# Sheet1.net
KiCad netlist of a schematic drawn in Altium Designer
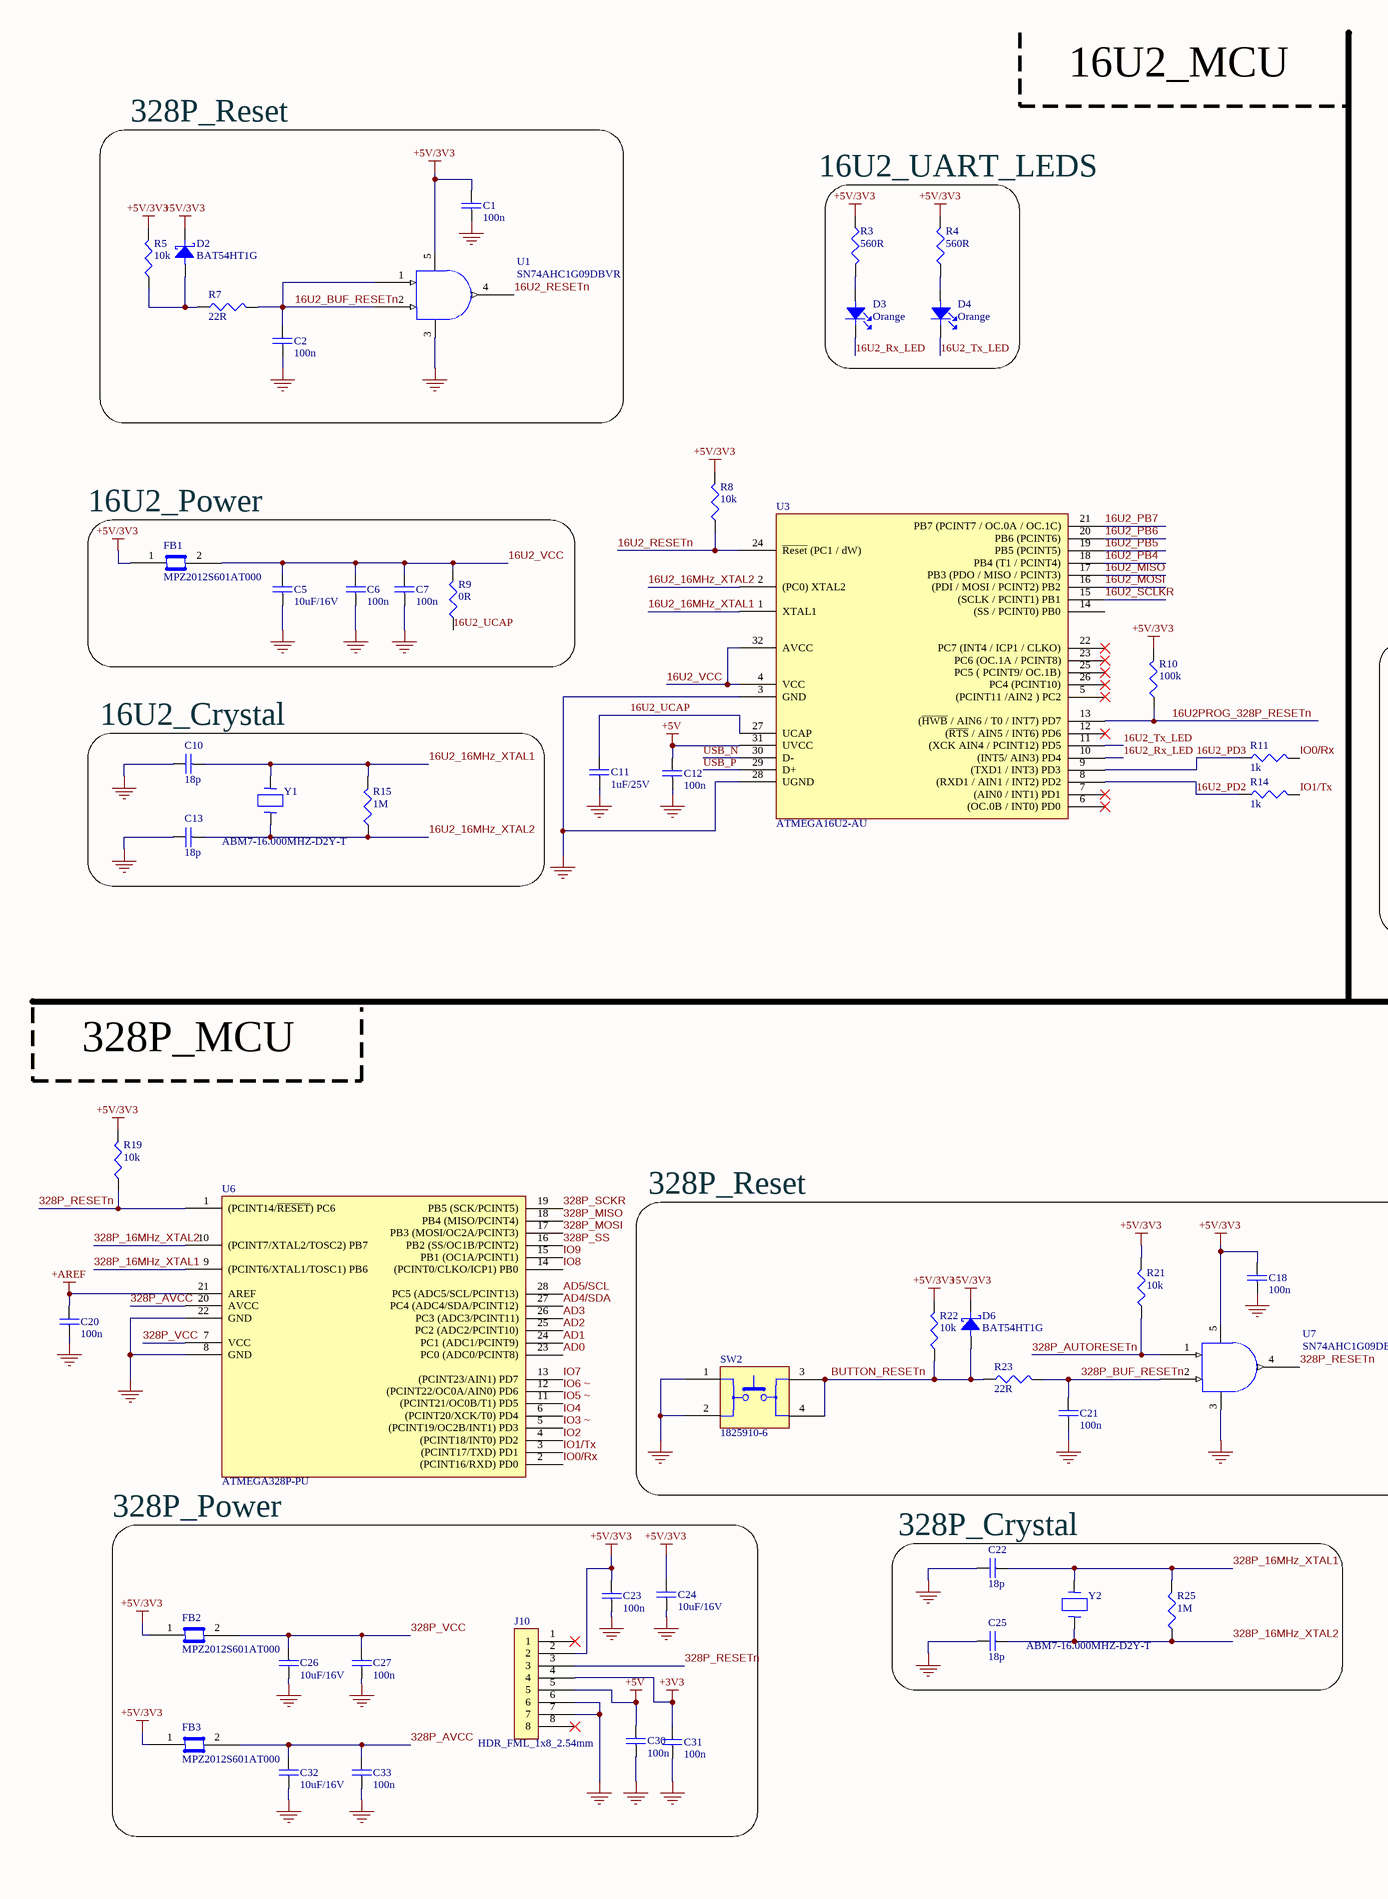
[diagram p0: Sheet1.SchDoc, left]
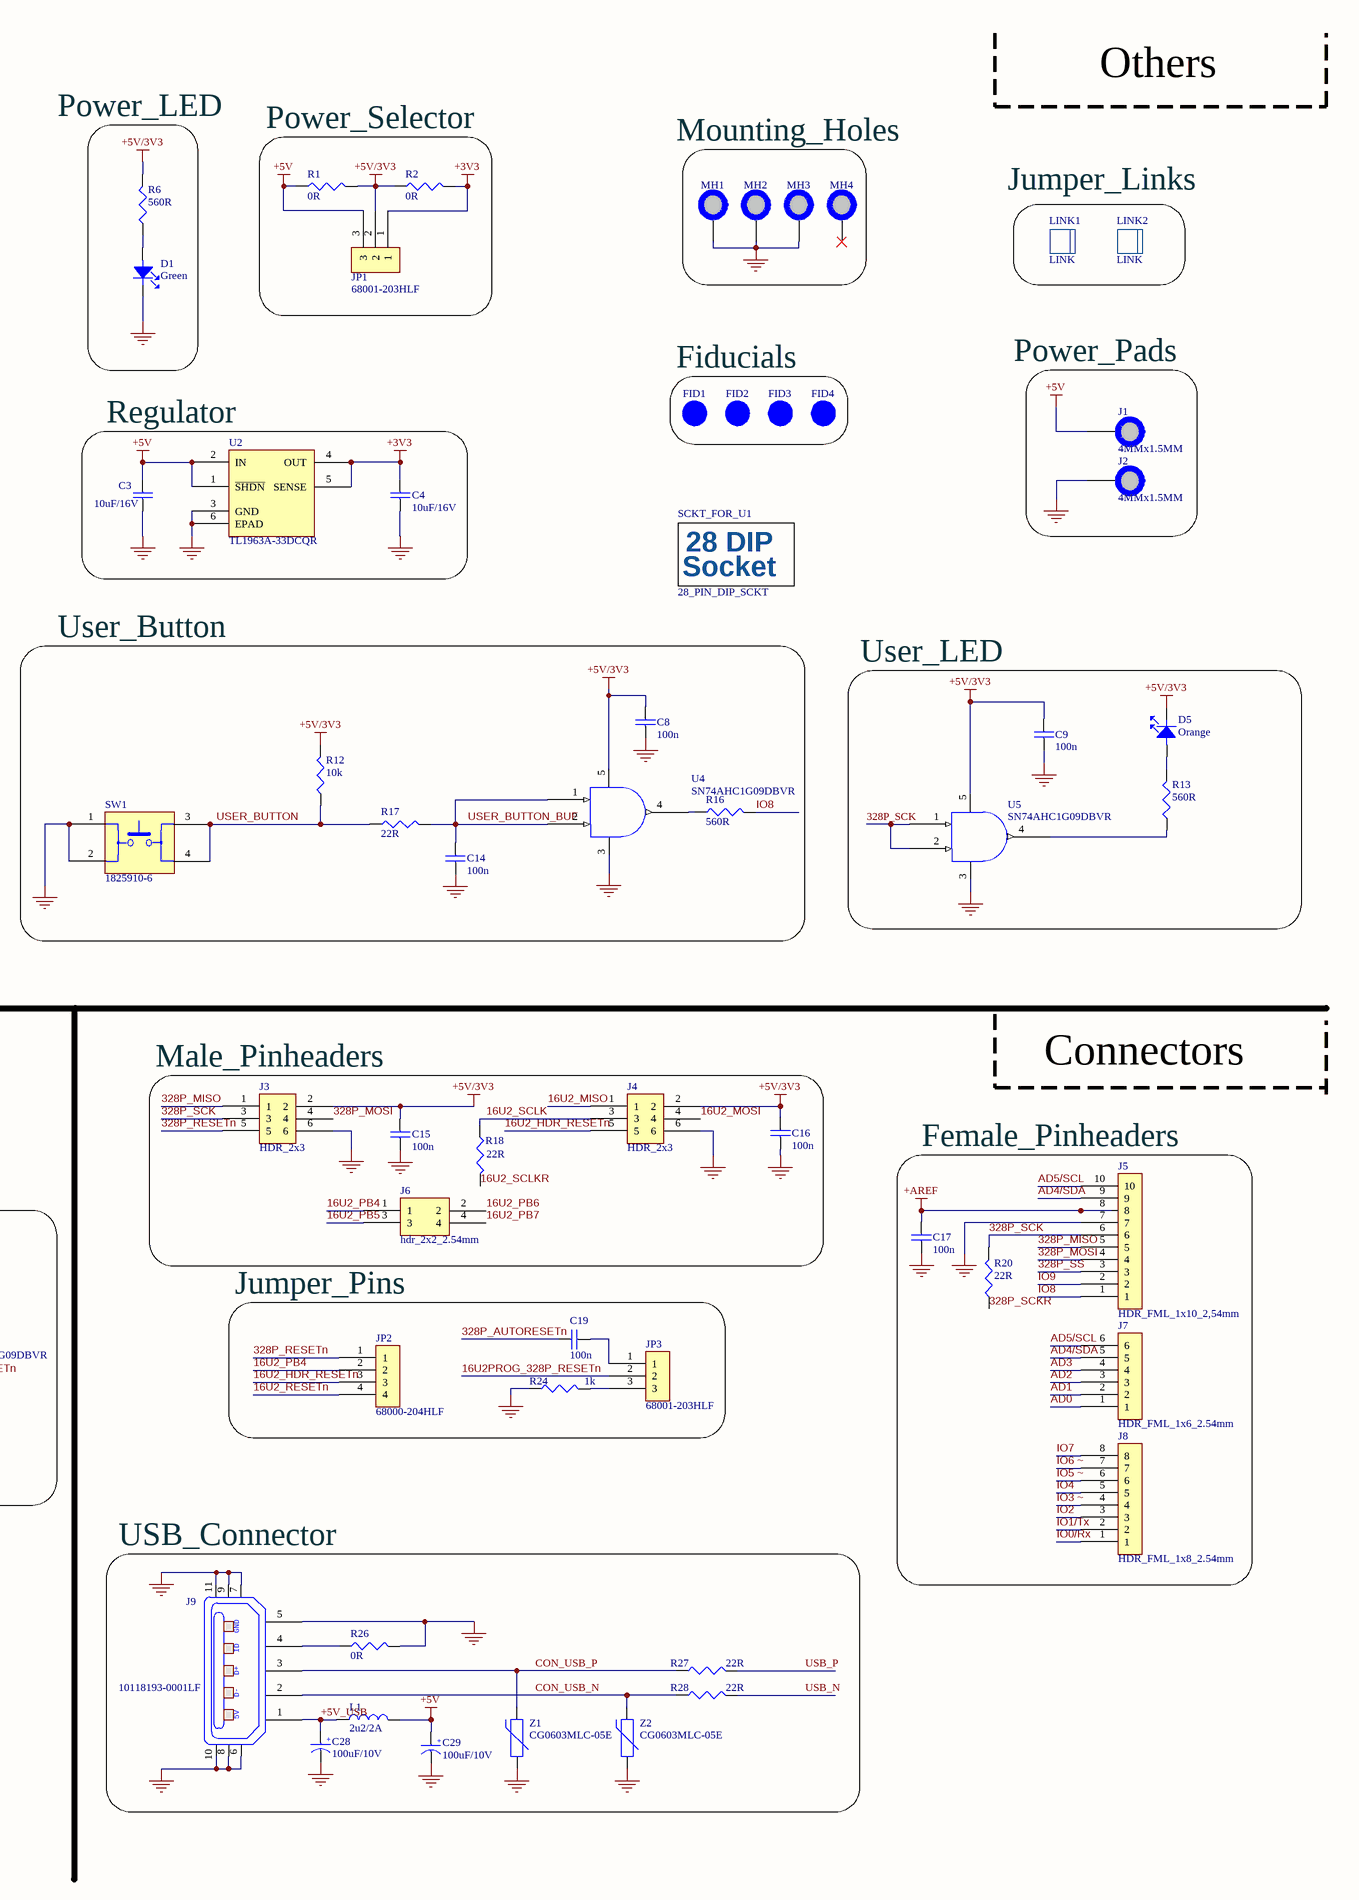
[diagram p1: Sheet1.SchDoc, right]

(export (version "E")
  (design (tool "Eeschema 10.0.6"))
  (components
    (comp (ref "C1")
      (value "100n")
      (footprint "C0805_100n")
      (description "Multilayer Ceramic Capacitor, 0.1 uF, 50 V, ± 10%, X7R, 0805 [2012 Metric]")
      (fields
        (field (name "MANUFACTURER") "TDK")
        (field (name "MANUFACTURER PART NUMBER") "C2012X7R1H104K085AA")
      )
      (libsource (lib "Schlib1") (part "capacitor_100n"))
    )
    (comp (ref "C2")
      (value "100n")
      (footprint "C0805_100n")
      (description "Multilayer Ceramic Capacitor, 0.1 uF, 50 V, ± 10%, X7R, 0805 [2012 Metric]")
      (fields
        (field (name "MANUFACTURER") "TDK")
        (field (name "MANUFACTURER PART NUMBER") "C2012X7R1H104K085AA")
      )
      (libsource (lib "Schlib1") (part "C2012X7R1H104K085AA"))
    )
    (comp (ref "C3")
      (value "10uF/16V")
      (footprint "C0805_10u")
      (description "C Series 0805 10 uF 16 V ±10 % Tolerance X5R SMT Multilayer Ceramic Capacitor")
      (fields
        (field (name "MANUFACTURER") "TDK")
        (field (name "MANUFACTURER PART NUMBER") "C2012X5R1C106K085AC")
      )
      (libsource (lib "Schlib1") (part "capacitor_10uF_16V"))
    )
    (comp (ref "C4")
      (value "10uF/16V")
      (footprint "C0805_10u")
      (description "C Series 0805 10 uF 16 V ±10 % Tolerance X5R SMT Multilayer Ceramic Capacitor")
      (fields
        (field (name "MANUFACTURER") "TDK")
        (field (name "MANUFACTURER PART NUMBER") "C2012X5R1C106K085AC")
      )
      (libsource (lib "Schlib1") (part "capacitor_10uF_16V"))
    )
    (comp (ref "C5")
      (value "10uF/16V")
      (footprint "C0805_10u")
      (description "C Series 0805 10 uF 16 V ±10 % Tolerance X5R SMT Multilayer Ceramic Capacitor")
      (fields
        (field (name "MANUFACTURER") "TDK")
        (field (name "MANUFACTURER PART NUMBER") "C2012X5R1C106K085AC")
      )
      (libsource (lib "Schlib1") (part "C2012X5R1C106K085AC"))
    )
    (comp (ref "C6")
      (value "100n")
      (footprint "C0805_100n")
      (description "Multilayer Ceramic Capacitor, 0.1 uF, 50 V, ± 10%, X7R, 0805 [2012 Metric]")
      (fields
        (field (name "MANUFACTURER") "TDK")
        (field (name "MANUFACTURER PART NUMBER") "C2012X7R1H104K085AA")
      )
      (libsource (lib "Schlib1") (part "C2012X7R1H104K085AA"))
    )
    (comp (ref "C7")
      (value "100n")
      (footprint "C0805_100n")
      (description "Multilayer Ceramic Capacitor, 0.1 uF, 50 V, ± 10%, X7R, 0805 [2012 Metric]")
      (fields
        (field (name "MANUFACTURER") "TDK")
        (field (name "MANUFACTURER PART NUMBER") "C2012X7R1H104K085AA")
      )
      (libsource (lib "Schlib1") (part "C2012X7R1H104K085AA"))
    )
    (comp (ref "C8")
      (value "100n")
      (footprint "C0805_100n")
      (description "Multilayer Ceramic Capacitor, 0.1 uF, 50 V, ± 10%, X7R, 0805 [2012 Metric]")
      (fields
        (field (name "MANUFACTURER") "TDK")
        (field (name "MANUFACTURER PART NUMBER") "C2012X7R1H104K085AA")
      )
      (libsource (lib "Schlib1") (part "capacitor_100n"))
    )
    (comp (ref "C9")
      (value "100n")
      (footprint "C0805_100n")
      (description "Multilayer Ceramic Capacitor, 0.1 uF, 50 V, ± 10%, X7R, 0805 [2012 Metric]")
      (fields
        (field (name "MANUFACTURER") "TDK")
        (field (name "MANUFACTURER PART NUMBER") "C2012X7R1H104K085AA")
      )
      (libsource (lib "Schlib1") (part "capacitor_100n"))
    )
    (comp (ref "C10")
      (value "18p")
      (footprint "C0805_100n")
      (description "Multilayer Ceramic Capacitor, 18 pF, 50 V, ± 10%, C0G (NP0), 0805 [2012 Metric]")
      (fields
        (field (name "MANUFACTURER") "KEMET")
        (field (name "MANUFACTURER PART NUMBER") "C0805C180K5GACTU")
      )
      (libsource (lib "Schlib1") (part "C0805C180K5GACTU"))
    )
    (comp (ref "C11")
      (value "1uF/25V")
      (footprint "C0805_10u")
      (description "Multilayer Ceramic Capacitor, 1 uF, 25 V, ± 10%, X7R, 0805 [2012 Metric]")
      (fields
        (field (name "MANUFACTURER") "TDK")
        (field (name "MANUFACTURER PART NUMBER") "CGA4J3X7R1E105K125AB")
      )
      (libsource (lib "Schlib1") (part "capacitor_1uF"))
    )
    (comp (ref "C12")
      (value "100n")
      (footprint "C0805_100n")
      (description "Multilayer Ceramic Capacitor, 0.1 uF, 50 V, ± 10%, X7R, 0805 [2012 Metric]")
      (fields
        (field (name "MANUFACTURER") "TDK")
        (field (name "MANUFACTURER PART NUMBER") "C2012X7R1H104K085AA")
      )
      (libsource (lib "Schlib1") (part "C2012X7R1H104K085AA"))
    )
    (comp (ref "C13")
      (value "18p")
      (footprint "C0805_100n")
      (description "Multilayer Ceramic Capacitor, 18 pF, 50 V, ± 10%, C0G (NP0), 0805 [2012 Metric]")
      (fields
        (field (name "MANUFACTURER") "KEMET")
        (field (name "MANUFACTURER PART NUMBER") "C0805C180K5GACTU")
      )
      (libsource (lib "Schlib1") (part "C0805C180K5GACTU"))
    )
    (comp (ref "C14")
      (value "100n")
      (footprint "C0805_100n")
      (description "Multilayer Ceramic Capacitor, 0.1 uF, 50 V, ± 10%, X7R, 0805 [2012 Metric]")
      (fields
        (field (name "MANUFACTURER") "TDK")
        (field (name "MANUFACTURER PART NUMBER") "C2012X7R1H104K085AA")
      )
      (libsource (lib "Schlib1") (part "C2012X7R1H104K085AA"))
    )
    (comp (ref "C15")
      (value "100n")
      (footprint "C0805_100n")
      (description "Multilayer Ceramic Capacitor, 0.1 uF, 50 V, ± 10%, X7R, 0805 [2012 Metric]")
      (fields
        (field (name "MANUFACTURER") "TDK")
        (field (name "MANUFACTURER PART NUMBER") "C2012X7R1H104K085AA")
      )
      (libsource (lib "Schlib1") (part "C2012X7R1H104K085AA"))
    )
    (comp (ref "C16")
      (value "100n")
      (footprint "C0805_100n")
      (description "Multilayer Ceramic Capacitor, 0.1 uF, 50 V, ± 10%, X7R, 0805 [2012 Metric]")
      (fields
        (field (name "MANUFACTURER") "TDK")
        (field (name "MANUFACTURER PART NUMBER") "C2012X7R1H104K085AA")
      )
      (libsource (lib "Schlib1") (part "C2012X7R1H104K085AA"))
    )
    (comp (ref "C17")
      (value "100n")
      (footprint "C0805_100n")
      (description "Multilayer Ceramic Capacitor, 0.1 uF, 50 V, ± 10%, X7R, 0805 [2012 Metric]")
      (fields
        (field (name "MANUFACTURER") "TDK")
        (field (name "MANUFACTURER PART NUMBER") "C2012X7R1H104K085AA")
      )
      (libsource (lib "Schlib1") (part "C2012X7R1H104K085AA"))
    )
    (comp (ref "C18")
      (value "100n")
      (footprint "C0805_100n")
      (description "Multilayer Ceramic Capacitor, 0.1 uF, 50 V, ± 10%, X7R, 0805 [2012 Metric]")
      (fields
        (field (name "MANUFACTURER") "TDK")
        (field (name "MANUFACTURER PART NUMBER") "C2012X7R1H104K085AA")
      )
      (libsource (lib "Schlib1") (part "capacitor_100n"))
    )
    (comp (ref "C19")
      (value "100n")
      (footprint "C0805_100n")
      (description "Multilayer Ceramic Capacitor, 0.1 uF, 50 V, ± 10%, X7R, 0805 [2012 Metric]")
      (fields
        (field (name "MANUFACTURER") "TDK")
        (field (name "MANUFACTURER PART NUMBER") "C2012X7R1H104K085AA")
      )
      (libsource (lib "Schlib1") (part "capacitor_100n"))
    )
    (comp (ref "C20")
      (value "100n")
      (footprint "C0805_100n")
      (description "Multilayer Ceramic Capacitor, 0.1 uF, 50 V, ± 10%, X7R, 0805 [2012 Metric]")
      (fields
        (field (name "MANUFACTURER") "TDK")
        (field (name "MANUFACTURER PART NUMBER") "C2012X7R1H104K085AA")
      )
      (libsource (lib "Schlib1") (part "C2012X7R1H104K085AA"))
    )
    (comp (ref "C21")
      (value "100n")
      (footprint "C0805_100n")
      (description "Multilayer Ceramic Capacitor, 0.1 uF, 50 V, ± 10%, X7R, 0805 [2012 Metric]")
      (fields
        (field (name "MANUFACTURER") "TDK")
        (field (name "MANUFACTURER PART NUMBER") "C2012X7R1H104K085AA")
      )
      (libsource (lib "Schlib1") (part "C2012X7R1H104K085AA"))
    )
    (comp (ref "C22")
      (value "18p")
      (footprint "C0805_100n")
      (description "Multilayer Ceramic Capacitor, 18 pF, 50 V, ± 10%, C0G (NP0), 0805 [2012 Metric]")
      (fields
        (field (name "MANUFACTURER") "KEMET")
        (field (name "MANUFACTURER PART NUMBER") "C0805C180K5GACTU")
      )
      (libsource (lib "Schlib1") (part "C0805C180K5GACTU"))
    )
    (comp (ref "C23")
      (value "100n")
      (footprint "C0805_100n")
      (description "Multilayer Ceramic Capacitor, 0.1 uF, 50 V, ± 10%, X7R, 0805 [2012 Metric]")
      (fields
        (field (name "MANUFACTURER") "TDK")
        (field (name "MANUFACTURER PART NUMBER") "C2012X7R1H104K085AA")
      )
      (libsource (lib "Schlib1") (part "C2012X7R1H104K085AA"))
    )
    (comp (ref "C24")
      (value "10uF/16V")
      (footprint "C0805_10u")
      (description "C Series 0805 10 uF 16 V ±10 % Tolerance X5R SMT Multilayer Ceramic Capacitor")
      (fields
        (field (name "MANUFACTURER") "TDK")
        (field (name "MANUFACTURER PART NUMBER") "C2012X5R1C106K085AC")
      )
      (libsource (lib "Schlib1") (part "C2012X5R1C106K085AC"))
    )
    (comp (ref "C25")
      (value "18p")
      (footprint "C0805_100n")
      (description "Multilayer Ceramic Capacitor, 18 pF, 50 V, ± 10%, C0G (NP0), 0805 [2012 Metric]")
      (fields
        (field (name "MANUFACTURER") "KEMET")
        (field (name "MANUFACTURER PART NUMBER") "C0805C180K5GACTU")
      )
      (libsource (lib "Schlib1") (part "C0805C180K5GACTU"))
    )
    (comp (ref "C26")
      (value "10uF/16V")
      (footprint "C0805_10u")
      (description "C Series 0805 10 uF 16 V ±10 % Tolerance X5R SMT Multilayer Ceramic Capacitor")
      (fields
        (field (name "MANUFACTURER") "TDK")
        (field (name "MANUFACTURER PART NUMBER") "C2012X5R1C106K085AC")
      )
      (libsource (lib "Schlib1") (part "C2012X5R1C106K085AC"))
    )
    (comp (ref "C27")
      (value "100n")
      (footprint "C0805_100n")
      (description "Multilayer Ceramic Capacitor, 0.1 uF, 50 V, ± 10%, X7R, 0805 [2012 Metric]")
      (fields
        (field (name "MANUFACTURER") "TDK")
        (field (name "MANUFACTURER PART NUMBER") "C2012X7R1H104K085AA")
      )
      (libsource (lib "Schlib1") (part "C2012X7R1H104K085AA"))
    )
    (comp (ref "C28")
      (value "100uF/10V")
      (footprint "C_ALU_C_SIZE")
      (description "Cap Aluminum Polymer 100uF 10VDC 20% (5 X 6mm) SMD 0.035 Ohm 1800mA 2000h 105C Automotive T/R")
      (fields
        (field (name "MANUFACTURER") "Nichicon")
        (field (name "MANUFACTURER PART NUMBER") "PCG1A101MCL1GS")
      )
      (libsource (lib "Schlib1") (part "capacitor_100uF/10V"))
    )
    (comp (ref "C29")
      (value "100uF/10V")
      (footprint "C_ALU_C_SIZE")
      (description "Cap Aluminum Polymer 100uF 10VDC 20% (5 X 6mm) SMD 0.035 Ohm 1800mA 2000h 105C Automotive T/R")
      (fields
        (field (name "MANUFACTURER") "Nichicon")
        (field (name "MANUFACTURER PART NUMBER") "PCG1A101MCL1GS")
      )
      (libsource (lib "Schlib1") (part "capacitor_100uF/10V"))
    )
    (comp (ref "C30")
      (value "100n")
      (footprint "C0805_100n")
      (description "Multilayer Ceramic Capacitor, 0.1 uF, 50 V, ± 10%, X7R, 0805 [2012 Metric]")
      (fields
        (field (name "MANUFACTURER") "TDK")
        (field (name "MANUFACTURER PART NUMBER") "C2012X7R1H104K085AA")
      )
      (libsource (lib "Schlib1") (part "C2012X7R1H104K085AA"))
    )
    (comp (ref "C31")
      (value "100n")
      (footprint "C0805_100n")
      (description "Multilayer Ceramic Capacitor, 0.1 uF, 50 V, ± 10%, X7R, 0805 [2012 Metric]")
      (fields
        (field (name "MANUFACTURER") "TDK")
        (field (name "MANUFACTURER PART NUMBER") "C2012X7R1H104K085AA")
      )
      (libsource (lib "Schlib1") (part "C2012X7R1H104K085AA"))
    )
    (comp (ref "C32")
      (value "10uF/16V")
      (footprint "C0805_10u")
      (description "C Series 0805 10 uF 16 V ±10 % Tolerance X5R SMT Multilayer Ceramic Capacitor")
      (fields
        (field (name "MANUFACTURER") "TDK")
        (field (name "MANUFACTURER PART NUMBER") "C2012X5R1C106K085AC")
      )
      (libsource (lib "Schlib1") (part "C2012X5R1C106K085AC"))
    )
    (comp (ref "C33")
      (value "100n")
      (footprint "C0805_100n")
      (description "Multilayer Ceramic Capacitor, 0.1 uF, 50 V, ± 10%, X7R, 0805 [2012 Metric]")
      (fields
        (field (name "MANUFACTURER") "TDK")
        (field (name "MANUFACTURER PART NUMBER") "C2012X7R1H104K085AA")
      )
      (libsource (lib "Schlib1") (part "C2012X7R1H104K085AA"))
    )
    (comp (ref "D1")
      (value "Green")
      (footprint "LED_0603")
      (description "Super Ultra Green 1.6 x 0.8 mm 120° Water Clear 50 mcd 2.2 V Surface Mount LED")
      (fields
        (field (name "MANUFACTURER") "Lumex")
        (field (name "MANUFACTURER PART NUMBER") "SML-LXFM0603SUGCTR")
      )
      (libsource (lib "Schlib1") (part "green_led"))
    )
    (comp (ref "D2")
      (value "BAT54HT1G")
      (footprint "SOD323")
      (description "Small Signal Schottky Diode, Single, 30 V, 200 Ma, 800 Mv, 600 Ma, 150 C")
      (fields (field (name "MANUFACTURER") "ON Semiconductor / Fairchild"))
      (libsource (lib "Schlib1") (part "BAT54HT1G"))
    )
    (comp (ref "D3")
      (value "Orange")
      (footprint "LED_0603")
      (description "LED Low-Power Uni-Color SB. Orange 611nm 1.8V 2-Pin SMD T/R")
      (fields
        (field (name "MANUFACTURER") "Kingbright")
        (field (name "MANUFACTURER PART NUMBER") "APT1608LSECK/J4-PRV")
      )
      (libsource (lib "Schlib1") (part "orange_led"))
    )
    (comp (ref "D4")
      (value "Orange")
      (footprint "LED_0603")
      (description "LED Low-Power Uni-Color SB. Orange 611nm 1.8V 2-Pin SMD T/R")
      (fields
        (field (name "MANUFACTURER") "Kingbright")
        (field (name "MANUFACTURER PART NUMBER") "APT1608LSECK/J4-PRV")
      )
      (libsource (lib "Schlib1") (part "orange_led"))
    )
    (comp (ref "D5")
      (value "Orange")
      (footprint "LED_0603")
      (description "LED Low-Power Uni-Color SB. Orange 611nm 1.8V 2-Pin SMD T/R")
      (fields
        (field (name "MANUFACTURER") "Kingbright")
        (field (name "MANUFACTURER PART NUMBER") "APT1608LSECK/J4-PRV")
      )
      (libsource (lib "Schlib1") (part "orange_led"))
    )
    (comp (ref "D6")
      (value "BAT54HT1G")
      (footprint "SOD323")
      (description "Small Signal Schottky Diode, Single, 30 V, 200 Ma, 800 Mv, 600 Ma, 150 C")
      (fields (field (name "MANUFACTURER") "ON Semiconductor / Fairchild"))
      (libsource (lib "Schlib1") (part "BAT54HT1G"))
    )
    (comp (ref "FB1")
      (value "MPZ2012S601AT000")
      (footprint "C0805_100n")
      (description "Ferrite Beads Multi-Layer Power 600Ohm 25% 100MHz 2A 100mOhm DCR 0805 T/R")
      (fields (field (name "MANUFACTURER") "TDK") (field (name "TOLERANCE") "25%"))
      (libsource (lib "Schlib1") (part "MPZ2012S601AT000"))
    )
    (comp (ref "FB2")
      (value "MPZ2012S601AT000")
      (footprint "C0805_100n")
      (description "Ferrite Beads Multi-Layer Power 600Ohm 25% 100MHz 2A 100mOhm DCR 0805 T/R")
      (fields (field (name "MANUFACTURER") "TDK") (field (name "TOLERANCE") "25%"))
      (libsource (lib "Schlib1") (part "MPZ2012S601AT000"))
    )
    (comp (ref "FB3")
      (value "MPZ2012S601AT000")
      (footprint "C0805_100n")
      (description "Ferrite Beads Multi-Layer Power 600Ohm 25% 100MHz 2A 100mOhm DCR 0805 T/R")
      (fields (field (name "MANUFACTURER") "TDK") (field (name "TOLERANCE") "25%"))
      (libsource (lib "Schlib1") (part "MPZ2012S601AT000"))
    )
    (comp (ref "FID1")
      (value "FID_1MM")
      (footprint "FID_40x120")
      (description "Fiducial 40mil Diameter, 120mil mask.")
      (libsource (lib "Schlib1") (part "FID_1MM"))
    )
    (comp (ref "FID2")
      (value "FID_1MM")
      (footprint "FID_40x120")
      (description "Fiducial 40mil Diameter, 120mil mask.")
      (libsource (lib "Schlib1") (part "FID_1MM"))
    )
    (comp (ref "FID3")
      (value "FID_1MM")
      (footprint "FID_40x120")
      (description "Fiducial 40mil Diameter, 120mil mask.")
      (libsource (lib "Schlib1") (part "FID_1MM"))
    )
    (comp (ref "FID4")
      (value "FID_1MM")
      (footprint "FID_40x120")
      (description "Fiducial 40mil Diameter, 120mil mask.")
      (libsource (lib "Schlib1") (part "FID_1MM"))
    )
    (comp (ref "J1")
      (value "4MMx1.5MM")
      (footprint "PAD_WITH_HOLE_4MMx1.5MM")
      (description "Pad with a whole 4mm x 1.5mm")
      (libsource (lib "Schlib1") (part "PAD_WITH_HOLE_4MMx1.5MM"))
    )
    (comp (ref "J2")
      (value "4MMx1.5MM")
      (footprint "PAD_WITH_HOLE_4MMx1.5MM")
      (description "Pad with a whole 4mm x 1.5mm")
      (libsource (lib "Schlib1") (part "PAD_WITH_HOLE_4MMx1.5MM"))
    )
    (comp (ref "J3")
      (value "HDR_2x3")
      (footprint "hdr_2x3_2.54mm")
      (description "Conn Unshrouded Header HDR 6 POS 2.54mm Solder ST Top Entry Thru-Hole BergStik® Bulk")
      (fields
        (field (name "MANUFACTURER") "Amphenol ICC / FCI")
        (field (name "MANUFACTURER PART NUMBER") "67997-206HLF")
      )
      (libsource (lib "Schlib1") (part "67997-206HLF"))
    )
    (comp (ref "J4")
      (value "HDR_2x3")
      (footprint "hdr_2x3_2.54mm")
      (description "Conn Unshrouded Header HDR 6 POS 2.54mm Solder ST Top Entry Thru-Hole BergStik® Bulk")
      (fields
        (field (name "MANUFACTURER") "Amphenol ICC / FCI")
        (field (name "MANUFACTURER PART NUMBER") "67997-206HLF")
      )
      (libsource (lib "Schlib1") (part "67997-206HLF"))
    )
    (comp (ref "J5")
      (value "HDR_FML_1x10_2,54mm")
      (footprint "hdr_fmale_1x10_2.54mm - duplicate")
      (description "2.54mm (0.1\") Pitch SIL Vertical PC Tail Socket Assembly, tin, 10 contacts")
      (fields (field (name "MANUFACTURER") "Harwin") (field (name "MANUFACTURER PART NUMBER") "M20-7821046"))
      (libsource (lib "Schlib1") (part "M20-7821046"))
    )
    (comp (ref "J6")
      (value "hdr_2x2_2.54mm")
      (footprint "hdr_2x2_2.54mm")
      (fields
        (field (name "MANUFACTURER") "Amphenol ICC / FCI")
        (field (name "MANUFACTURER PART NUMBER") "77313-118-04LF")
      )
      (libsource (lib "Schlib1") (part "77313-118-04LF"))
    )
    (comp (ref "J7")
      (value "HDR_FML_1x6_2.54mm")
      (footprint "hdr_fmale_1x6_2.54mm")
      (description "2.54mm (0.1\") Pitch SIL Vertical PC Tail Socket Assembly, tin, 6 contacts")
      (fields (field (name "MANUFACTURER") "Harwin") (field (name "MANUFACTURER PART NUMBER") "M20-7820646"))
      (libsource (lib "Schlib1") (part "M20-7820646"))
    )
    (comp (ref "J8")
      (value "HDR_FML_1x8_2.54mm")
      (footprint "hdr_fmale_1x8_2.54mm")
      (description "2.54mm (0.1\") Pitch SIL Vertical PC Tail Socket Assembly, selective gold + tin, 8 contacts")
      (fields (field (name "MANUFACTURER") "Harwin") (field (name "MANUFACTURER PART NUMBER") "M20-7820842"))
      (libsource (lib "Schlib1") (part "M20-7820842"))
    )
    (comp (ref "J9")
      (value "10118193-0001LF")
      (footprint "10118193")
      (description "Usb Connector, 5 Contact(S), Female, Right Angle, Surface Mount Terminal, Locking, Receptacle")
      (fields (field (name "MANUFACTURER") "Amphenol Communications Solutions"))
      (libsource (lib "Schlib1") (part "10118193-0001LF"))
    )
    (comp (ref "J10")
      (value "HDR_FML_1x8_2.54mm")
      (footprint "hdr_fmale_1x8_2.54mm")
      (description "2.54mm (0.1\") Pitch SIL Vertical PC Tail Socket Assembly, selective gold + tin, 8 contacts")
      (fields (field (name "MANUFACTURER") "Harwin") (field (name "MANUFACTURER PART NUMBER") "M20-7820842"))
      (libsource (lib "") (part "M20-7820842_1"))
    )
    (comp (ref "JP1")
      (value "68001-203HLF")
      (footprint "hdr_1x3_2.54mm")
      (description "Conn Unshrouded Header HDR 3 POS 2.54mm Solder ST Top Entry Thru-Hole BergStik® Bulk")
      (fields (field (name "MANUFACTURER") "Amphenol ICC / FCI"))
      (libsource (lib "Schlib1") (part "HDR_1x3_2.54mm"))
    )
    (comp (ref "JP2")
      (value "68000-204HLF")
      (footprint "hdr_1x4_2.54mm")
      (description "Conn Unshrouded Header HDR 4 POS 2.54mm Solder ST Top Entry Thru-Hole BergStik® Bulk")
      (fields (field (name "MANUFACTURER") "Amphenol ICC / FCI"))
      (libsource (lib "Schlib1") (part "HDR_1x4_2.54mm"))
    )
    (comp (ref "JP3")
      (value "68001-203HLF")
      (footprint "hdr_1x3_2.54mm")
      (description "Conn Unshrouded Header HDR 3 POS 2.54mm Solder ST Top Entry Thru-Hole BergStik® Bulk")
      (fields (field (name "MANUFACTURER") "Amphenol ICC / FCI"))
      (libsource (lib "") (part "HDR_1x3_2.54mm_1"))
    )
    (comp (ref "L1")
      (value "2u2/2A")
      (footprint "C1210_IND")
      (description "General Purpose Inductor, 2.2uH, 20%, 1 Element, Ferrite-Core, SMD, 1210")
      (fields
        (field (name "MANUFACTURER") "KEMET")
        (field (name "MANUFACTURER PART NUMBER") "L1210R2R2MDWIT")
      )
      (libsource (lib "Schlib1") (part "inductor_2.2uH"))
    )
    (comp (ref "LINK1")
      (value "LINK")
      (description "2 Position 2.54 mm Centerline Single Circuit Open Top Jumper")
      (fields
        (field (name "MANUFACTURER") "Sullins")
        (field (name "MANUFACTURER PART NUMBER") "QPC02SXGN-RC")
      )
      (libsource (lib "Schlib1") (part "link"))
    )
    (comp (ref "LINK2")
      (value "LINK")
      (description "2 Position 2.54 mm Centerline Single Circuit Open Top Jumper")
      (fields
        (field (name "MANUFACTURER") "Sullins")
        (field (name "MANUFACTURER PART NUMBER") "QPC02SXGN-RC")
      )
      (libsource (lib "Schlib1") (part "link"))
    )
    (comp (ref "MH1")
      (value "MH_7.4MMC_3.2MMD")
      (footprint "MH_7.4MMC_3.2MMD")
      (description "Mounting hole 7.4mm diameter 3.2mm drill.")
      (libsource (lib "Schlib1") (part "MH_7.4MMC_3.2MMD"))
    )
    (comp (ref "MH2")
      (value "MH_7.4MMC_3.2MMD")
      (footprint "MH_7.4MMC_3.2MMD")
      (description "Mounting hole 7.4mm diameter 3.2mm drill.")
      (libsource (lib "Schlib1") (part "MH_7.4MMC_3.2MMD"))
    )
    (comp (ref "MH3")
      (value "MH_7.4MMC_3.2MMD")
      (footprint "MH_7.4MMC_3.2MMD")
      (description "Mounting hole 7.4mm diameter 3.2mm drill.")
      (libsource (lib "Schlib1") (part "MH_7.4MMC_3.2MMD"))
    )
    (comp (ref "MH4")
      (value "MH_7.4MMNC_3.2MMD")
      (footprint "MH_7.4MMNC_3.2MMD")
      (description "Mounted hole 7.4mm diamater non copper 3.2mm drill")
      (libsource (lib "Schlib1") (part "MH_7.4MMNC_3.2MMD"))
    )
    (comp (ref "R1")
      (value "0R")
      (footprint "R0805")
      (description "Zero Ohm Resistor, Jumper, 0805 [2012 Metric], Thick Film, 125 mW, 2 A, Surface Mount")
      (fields
        (field (name "MANUFACTURER") "Bourns")
        (field (name "MANUFACTURER PART NUMBER") "CR0805AJ/-000EAS")
      )
      (libsource (lib "Schlib1") (part "CR0805AJ/-000EAS"))
    )
    (comp (ref "R2")
      (value "0R")
      (footprint "R0805")
      (description "Zero Ohm Resistor, Jumper, 0805 [2012 Metric], Thick Film, 125 mW, 2 A, Surface Mount")
      (fields
        (field (name "MANUFACTURER") "Bourns")
        (field (name "MANUFACTURER PART NUMBER") "CR0805AJ/-000EAS")
      )
      (libsource (lib "Schlib1") (part "CR0805AJ/-000EAS"))
    )
    (comp (ref "R3")
      (value "560R")
      (footprint "R0805")
      (description "Res Thick Film 0805 560 Ohm 1% 1/8W ±100ppm/°C Molded SMD SMD Paper T/R")
      (fields
        (field (name "MANUFACTURER") "Yageo")
        (field (name "MANUFACTURER PART NUMBER") "RC0805FR-10560RL")
      )
      (libsource (lib "Schlib1") (part "RC0805FR-10560RL"))
    )
    (comp (ref "R4")
      (value "560R")
      (footprint "R0805")
      (description "Res Thick Film 0805 560 Ohm 1% 1/8W ±100ppm/°C Molded SMD SMD Paper T/R")
      (fields
        (field (name "MANUFACTURER") "Yageo")
        (field (name "MANUFACTURER PART NUMBER") "RC0805FR-10560RL")
      )
      (libsource (lib "Schlib1") (part "RC0805FR-10560RL"))
    )
    (comp (ref "R5")
      (value "10k")
      (footprint "R0805")
      (description "SMD Chip Resistor, 10 kOhm, ± 1%, 125 mW, 0805 [2012 Metric], Thick Film, General Purpose")
      (fields
        (field (name "MANUFACTURER") "Yageo")
        (field (name "MANUFACTURER PART NUMBER") "RC0805FR-0710KL")
      )
      (libsource (lib "Schlib1") (part "RC0805FR-0710KL"))
    )
    (comp (ref "R6")
      (value "560R")
      (footprint "R0805")
      (description "Res Thick Film 0805 560 Ohm 1% 1/8W ±100ppm/°C Molded SMD SMD Paper T/R")
      (fields
        (field (name "MANUFACTURER") "Yageo")
        (field (name "MANUFACTURER PART NUMBER") "RC0805FR-10560RL")
      )
      (libsource (lib "Schlib1") (part "RC0805FR-10560RL"))
    )
    (comp (ref "R7")
      (value "22R")
      (footprint "R0805")
      (description "SMD Chip Resistor, 22 Ohm, ± 1%, 125 mW, 0805 [2012 Metric], Thick Film, General Purpose")
      (fields
        (field (name "MANUFACTURER") "Yageo")
        (field (name "MANUFACTURER PART NUMBER") "RC0805FR-0722RL")
      )
      (libsource (lib "Schlib1") (part "RC0805FR-0722RL"))
    )
    (comp (ref "R8")
      (value "10k")
      (footprint "R0805")
      (description "SMD Chip Resistor, 10 kOhm, ± 1%, 125 mW, 0805 [2012 Metric], Thick Film, General Purpose")
      (fields
        (field (name "MANUFACTURER") "Yageo")
        (field (name "MANUFACTURER PART NUMBER") "RC0805FR-0710KL")
      )
      (libsource (lib "Schlib1") (part "RC0805FR-0710KL"))
    )
    (comp (ref "R9")
      (value "0R")
      (footprint "R0805")
      (description "Zero Ohm Resistor, Jumper, 0805 [2012 Metric], Thick Film, 125 mW, 2 A, Surface Mount")
      (fields
        (field (name "MANUFACTURER") "Bourns")
        (field (name "MANUFACTURER PART NUMBER") "CR0805AJ/-000EAS")
      )
      (libsource (lib "Schlib1") (part "CR0805AJ/-000EAS"))
    )
    (comp (ref "R10")
      (value "100k")
      (footprint "R0805")
      (description "SMD Chip Resistor, 100 kOhm, ± 1%, 125 mW, 0805 [2012 Metric], Thick Film, General Purpose")
      (fields
        (field (name "MANUFACTURER") "Yageo")
        (field (name "MANUFACTURER PART NUMBER") "RC0805FR-07100KL")
      )
      (libsource (lib "Schlib1") (part "RC0805FR-07100KL"))
    )
    (comp (ref "R11")
      (value "1k")
      (footprint "R0805")
      (description "SMD Chip Resistor, 1 kOhm, ± 1%, 125 mW, 0805 [2012 Metric], Thick Film, General Purpose")
      (fields
        (field (name "MANUFACTURER") "Yageo")
        (field (name "MANUFACTURER PART NUMBER") "RC0805FR-101KL")
      )
      (libsource (lib "Schlib1") (part "RC0805FR-101KL"))
    )
    (comp (ref "R12")
      (value "10k")
      (footprint "R0805")
      (description "SMD Chip Resistor, 10 kOhm, ± 1%, 125 mW, 0805 [2012 Metric], Thick Film, General Purpose")
      (fields
        (field (name "MANUFACTURER") "Yageo")
        (field (name "MANUFACTURER PART NUMBER") "RC0805FR-0710KL")
      )
      (libsource (lib "Schlib1") (part "RC0805FR-0710KL"))
    )
    (comp (ref "R13")
      (value "560R")
      (footprint "R0805")
      (description "Res Thick Film 0805 560 Ohm 1% 1/8W ±100ppm/°C Molded SMD SMD Paper T/R")
      (fields
        (field (name "MANUFACTURER") "Yageo")
        (field (name "MANUFACTURER PART NUMBER") "RC0805FR-10560RL")
      )
      (libsource (lib "Schlib1") (part "RC0805FR-10560RL"))
    )
    (comp (ref "R14")
      (value "1k")
      (footprint "R0805")
      (description "SMD Chip Resistor, 1 kOhm, ± 1%, 125 mW, 0805 [2012 Metric], Thick Film, General Purpose")
      (fields
        (field (name "MANUFACTURER") "Yageo")
        (field (name "MANUFACTURER PART NUMBER") "RC0805FR-101KL")
      )
      (libsource (lib "Schlib1") (part "RC0805FR-101KL"))
    )
    (comp (ref "R15")
      (value "1M")
      (footprint "R0805")
      (description "SMD Chip Resistor, 1 MOhm, ± 1%, 125 mW, 0805 [2012 Metric], Thick Film, General Purpose")
      (fields
        (field (name "MANUFACTURER") "Yageo")
        (field (name "MANUFACTURER PART NUMBER") "RC0805FR-071ML")
      )
      (libsource (lib "Schlib1") (part "RC0805FR-071ML"))
    )
    (comp (ref "R16")
      (value "560R")
      (footprint "R0805")
      (description "Res Thick Film 0805 560 Ohm 1% 1/8W ±100ppm/°C Molded SMD SMD Paper T/R")
      (fields
        (field (name "MANUFACTURER") "Yageo")
        (field (name "MANUFACTURER PART NUMBER") "RC0805FR-10560RL")
      )
      (libsource (lib "Schlib1") (part "RC0805FR-10560RL"))
    )
    (comp (ref "R17")
      (value "22R")
      (footprint "R0805")
      (description "SMD Chip Resistor, 22 Ohm, ± 1%, 125 mW, 0805 [2012 Metric], Thick Film, General Purpose")
      (fields
        (field (name "MANUFACTURER") "Yageo")
        (field (name "MANUFACTURER PART NUMBER") "RC0805FR-0722RL")
      )
      (libsource (lib "Schlib1") (part "RC0805FR-0722RL"))
    )
    (comp (ref "R18")
      (value "22R")
      (footprint "R0805")
      (description "SMD Chip Resistor, 22 Ohm, ± 1%, 125 mW, 0805 [2012 Metric], Thick Film, General Purpose")
      (fields
        (field (name "MANUFACTURER") "Yageo")
        (field (name "MANUFACTURER PART NUMBER") "RC0805FR-0722RL")
      )
      (libsource (lib "Schlib1") (part "RC0805FR-0722RL"))
    )
    (comp (ref "R19")
      (value "10k")
      (footprint "R0805")
      (description "SMD Chip Resistor, 10 kOhm, ± 1%, 125 mW, 0805 [2012 Metric], Thick Film, General Purpose")
      (fields
        (field (name "MANUFACTURER") "Yageo")
        (field (name "MANUFACTURER PART NUMBER") "RC0805FR-0710KL")
      )
      (libsource (lib "Schlib1") (part "RC0805FR-0710KL"))
    )
    (comp (ref "R20")
      (value "22R")
      (footprint "R0805")
      (description "SMD Chip Resistor, 22 Ohm, ± 1%, 125 mW, 0805 [2012 Metric], Thick Film, General Purpose")
      (fields
        (field (name "MANUFACTURER") "Yageo")
        (field (name "MANUFACTURER PART NUMBER") "RC0805FR-0722RL")
      )
      (libsource (lib "Schlib1") (part "RC0805FR-0722RL"))
    )
    (comp (ref "R21")
      (value "10k")
      (footprint "R0805")
      (description "SMD Chip Resistor, 10 kOhm, ± 1%, 125 mW, 0805 [2012 Metric], Thick Film, General Purpose")
      (fields
        (field (name "MANUFACTURER") "Yageo")
        (field (name "MANUFACTURER PART NUMBER") "RC0805FR-0710KL")
      )
      (libsource (lib "Schlib1") (part "RC0805FR-0710KL"))
    )
    (comp (ref "R22")
      (value "10k")
      (footprint "R0805")
      (description "SMD Chip Resistor, 10 kOhm, ± 1%, 125 mW, 0805 [2012 Metric], Thick Film, General Purpose")
      (fields
        (field (name "MANUFACTURER") "Yageo")
        (field (name "MANUFACTURER PART NUMBER") "RC0805FR-0710KL")
      )
      (libsource (lib "Schlib1") (part "RC0805FR-0710KL"))
    )
    (comp (ref "R23")
      (value "22R")
      (footprint "R0805")
      (description "SMD Chip Resistor, 22 Ohm, ± 1%, 125 mW, 0805 [2012 Metric], Thick Film, General Purpose")
      (fields
        (field (name "MANUFACTURER") "Yageo")
        (field (name "MANUFACTURER PART NUMBER") "RC0805FR-0722RL")
      )
      (libsource (lib "Schlib1") (part "RC0805FR-0722RL"))
    )
    (comp (ref "R24")
      (value "1k")
      (footprint "R0805")
      (description "SMD Chip Resistor, 1 kOhm, ± 1%, 125 mW, 0805 [2012 Metric], Thick Film, General Purpose")
      (fields
        (field (name "MANUFACTURER") "Yageo")
        (field (name "MANUFACTURER PART NUMBER") "RC0805FR-101KL")
      )
      (libsource (lib "Schlib1") (part "RC0805FR-101KL"))
    )
    (comp (ref "R25")
      (value "1M")
      (footprint "R0805")
      (description "SMD Chip Resistor, 1 MOhm, ± 1%, 125 mW, 0805 [2012 Metric], Thick Film, General Purpose")
      (fields
        (field (name "MANUFACTURER") "Yageo")
        (field (name "MANUFACTURER PART NUMBER") "RC0805FR-071ML")
      )
      (libsource (lib "Schlib1") (part "RC0805FR-071ML"))
    )
    (comp (ref "R26")
      (value "0R")
      (footprint "R0805")
      (description "Zero Ohm Resistor, Jumper, 0805 [2012 Metric], Thick Film, 125 mW, 2 A, Surface Mount")
      (fields
        (field (name "MANUFACTURER") "Bourns")
        (field (name "MANUFACTURER PART NUMBER") "CR0805AJ/-000EAS")
      )
      (libsource (lib "Schlib1") (part "CR0805AJ/-000EAS"))
    )
    (comp (ref "R27")
      (value "22R")
      (footprint "R0805")
      (description "SMD Chip Resistor, 22 Ohm, ± 1%, 125 mW, 0805 [2012 Metric], Thick Film, General Purpose")
      (fields
        (field (name "MANUFACTURER") "Yageo")
        (field (name "MANUFACTURER PART NUMBER") "RC0805FR-0722RL")
      )
      (libsource (lib "Schlib1") (part "RC0805FR-0722RL"))
    )
    (comp (ref "R28")
      (value "22R")
      (footprint "R0805")
      (description "SMD Chip Resistor, 22 Ohm, ± 1%, 125 mW, 0805 [2012 Metric], Thick Film, General Purpose")
      (fields
        (field (name "MANUFACTURER") "Yageo")
        (field (name "MANUFACTURER PART NUMBER") "RC0805FR-0722RL")
      )
      (libsource (lib "Schlib1") (part "RC0805FR-0722RL"))
    )
    (comp (ref "SCKT_FOR_U1")
      (value "28_PIN_DIP_SCKT")
      (footprint "28_DIP_7.26mm_SCKT")
      (description "Socket DIP 28Cnts DualWipe 0.3InSpc. PhosphorBronze Nickel KinkedTail 4800Series ¦ 3M 4828-3004-CP")
      (fields (field (name "MANUFACTURER") "3M") (field (name "MANUFACTURER PART NUMBER") "4828-3004-CP"))
      (libsource (lib "Schlib1") (part "28_dip_socket"))
    )
    (comp (ref "SW1")
      (value "1825910-6")
      (footprint "1825910-6")
      (description "Alcoswitch, Switch, Pushbutton, Tactile, SPST, 50mA, Thru Hole, 6mm ¦ TE Connectivity FSM4JH")
      (fields (field (name "MANUFACTURER") "TE Connectivity Alcoswitch"))
      (libsource (lib "Schlib1") (part "1825910-6"))
    )
    (comp (ref "SW2")
      (value "1825910-6")
      (footprint "1825910-6")
      (description "Alcoswitch, Switch, Pushbutton, Tactile, SPST, 50mA, Thru Hole, 6mm ¦ TE Connectivity FSM4JH")
      (fields (field (name "MANUFACTURER") "TE Connectivity Alcoswitch"))
      (libsource (lib "Schlib1") (part "1825910-6"))
    )
    (comp (ref "U1")
      (value "SN74AHC1G09DBVR")
      (footprint "DBV_SOT_23_5")
      (description "1-ch, 2-input 2-V to 5.5-V high-speed (9 ns) AND gate with open-drain outputs 5-SOT-23 -55 to 125")
      (fields (field (name "MANUFACTURER") "Texas Instruments"))
      (libsource (lib "Schlib1") (part "AND_GATE"))
    )
    (comp (ref "U2")
      (value "TL1963A-33DCQR")
      (footprint "DCQ (R-PDSO-G6)")
      (description "LDO Regulator Pos 3.3V 1.5A 6-Pin(5+Tab) SOT-223 T/R")
      (fields (field (name "MANUFACTURER") "Texas Instruments"))
      (libsource (lib "Schlib1") (part "+3.3V_LDO_REG"))
    )
    (comp (ref "U3")
      (value "ATMEGA16U2-AU")
      (footprint "TQFP32")
      (description "8-bit AVR MCU, 16 KB, 512 Bytes, 16 MHz, 2.7 to 5.5V, TQFP-32, RoHS")
      (fields
        (field (name "MANUFACTURER") "Microchip")
        (field (name "MANUFACTURER PART NUMBER") "ATMEGA16U2-AUR")
      )
      (libsource (lib "Schlib1") (part "ATMEGA16U2-AUR"))
    )
    (comp (ref "U4")
      (value "SN74AHC1G09DBVR")
      (footprint "DBV_SOT_23_5")
      (description "1-ch, 2-input 2-V to 5.5-V high-speed (9 ns) AND gate with open-drain outputs 5-SOT-23 -55 to 125")
      (fields (field (name "MANUFACTURER") "Texas Instruments"))
      (libsource (lib "Schlib1") (part "AND_GATE"))
    )
    (comp (ref "U5")
      (value "SN74AHC1G09DBVR")
      (footprint "DBV_SOT_23_5")
      (description "1-ch, 2-input 2-V to 5.5-V high-speed (9 ns) AND gate with open-drain outputs 5-SOT-23 -55 to 125")
      (fields (field (name "MANUFACTURER") "Texas Instruments"))
      (libsource (lib "Schlib1") (part "AND_GATE"))
    )
    (comp (ref "U6")
      (value "ATMEGA328P-PU")
      (footprint "DIP28")
      (description "Microchip - ATMEGA328P-PU - Microcontroller Mcu, 8 Bit, Atmega, 20MHZ, DIP-28")
      (fields (field (name "MANUFACTURER") "Microchip"))
      (libsource (lib "Schlib1") (part "ATMEGA328P-PU"))
    )
    (comp (ref "U7")
      (value "SN74AHC1G09DBVR")
      (footprint "DBV_SOT_23_5")
      (description "1-ch, 2-input 2-V to 5.5-V high-speed (9 ns) AND gate with open-drain outputs 5-SOT-23 -55 to 125")
      (fields (field (name "MANUFACTURER") "Texas Instruments"))
      (libsource (lib "Schlib1") (part "AND_GATE"))
    )
    (comp (ref "Y1")
      (value "ABM7-16.000MHZ-D2Y-T")
      (footprint "ABM7_v1_1_BIG")
      (description "Crystal 16MHz ±20ppm (Tol) ±30ppm (Stability) 18pF FUND 50Ohm 2-Pin Mini-CSMD T/R")
      (fields (field (name "MANUFACTURER") "Abracon"))
      (libsource (lib "Schlib1") (part "ABM7-16.000MHZ-D2Y-T"))
    )
    (comp (ref "Y2")
      (value "ABM7-16.000MHZ-D2Y-T")
      (footprint "ABM7_v1_1_BIG")
      (description "Crystal 16MHz ±20ppm (Tol) ±30ppm (Stability) 18pF FUND 50Ohm 2-Pin Mini-CSMD T/R")
      (fields (field (name "MANUFACTURER") "Abracon"))
      (libsource (lib "Schlib1") (part "ABM7-16.000MHZ-D2Y-T"))
    )
    (comp (ref "Z1")
      (value "CG0603MLC-05E")
      (footprint "R0603")
      (description "ESD Suppressor Multilayer Varistor 5V Automotive 2-Pin Case 0603(1608Metric) T/R")
      (fields (field (name "MANUFACTURER") "Bourns") (field (name "VOLTAGE") "5V"))
      (libsource (lib "Schlib1") (part "varasitor"))
    )
    (comp (ref "Z2")
      (value "CG0603MLC-05E")
      (footprint "R0603")
      (description "ESD Suppressor Multilayer Varistor 5V Automotive 2-Pin Case 0603(1608Metric) T/R")
      (fields (field (name "MANUFACTURER") "Bourns") (field (name "VOLTAGE") "5V"))
      (libsource (lib "Schlib1") (part "varasitor"))
    )
  )
  (nets
    (net (code "1") (name "+3V3") (class "Default")
      (node (ref "C31") (pin "2") (pinfunction "2_2") (pintype "passive"))
      (node (ref "C4") (pin "2") (pinfunction "2_2") (pintype "passive"))
      (node (ref "J10") (pin "4") (pinfunction "4_4") (pintype "passive"))
      (node (ref "JP1") (pin "1") (pinfunction "1_1") (pintype "passive"))
      (node (ref "R2") (pin "2") (pinfunction "2_2") (pintype "passive"))
      (node (ref "U2") (pin "4") (pinfunction "OUT_4") (pintype "passive"))
      (node (ref "U2") (pin "5") (pinfunction "SENSE_5") (pintype "passive"))
    )
    (net (code "2") (name "+5V") (class "Default")
      (node (ref "C12") (pin "2") (pinfunction "2_2") (pintype "passive"))
      (node (ref "C29") (pin "1") (pinfunction "1_1") (pintype "passive"))
      (node (ref "C3") (pin "2") (pinfunction "2_2") (pintype "passive"))
      (node (ref "C30") (pin "2") (pinfunction "2_2") (pintype "passive"))
      (node (ref "J1") (pin "1") (pinfunction "1_1") (pintype "passive"))
      (node (ref "J10") (pin "5") (pinfunction "5_5") (pintype "passive"))
      (node (ref "JP1") (pin "3") (pinfunction "3_3") (pintype "passive"))
      (node (ref "L1") (pin "2") (pinfunction "2_2") (pintype "passive"))
      (node (ref "R1") (pin "1") (pinfunction "1_1") (pintype "passive"))
      (node (ref "U2") (pin "1") (pinfunction "~{SHDN}_1") (pintype "passive"))
      (node (ref "U2") (pin "2") (pinfunction "IN_2") (pintype "passive"))
      (node (ref "U3") (pin "31") (pinfunction "UVCC_31") (pintype "passive"))
    )
    (net (code "3") (name "+5V{slash}3V3") (class "Default")
      (node (ref "C1") (pin "2") (pinfunction "2_2") (pintype "passive"))
      (node (ref "C15") (pin "2") (pinfunction "2_2") (pintype "passive"))
      (node (ref "C16") (pin "2") (pinfunction "2_2") (pintype "passive"))
      (node (ref "C18") (pin "2") (pinfunction "2_2") (pintype "passive"))
      (node (ref "C23") (pin "2") (pinfunction "2_2") (pintype "passive"))
      (node (ref "C24") (pin "2") (pinfunction "2_2") (pintype "passive"))
      (node (ref "C8") (pin "2") (pinfunction "2_2") (pintype "passive"))
      (node (ref "C9") (pin "2") (pinfunction "2_2") (pintype "passive"))
      (node (ref "D2") (pin "1") (pinfunction "Cathode_1") (pintype "passive"))
      (node (ref "D5") (pin "1") (pinfunction "Cathode_1") (pintype "passive"))
      (node (ref "D6") (pin "1") (pinfunction "Cathode_1") (pintype "passive"))
      (node (ref "FB1") (pin "1") (pinfunction "1_1") (pintype "passive"))
      (node (ref "FB2") (pin "1") (pinfunction "1_1") (pintype "passive"))
      (node (ref "FB3") (pin "1") (pinfunction "1_1") (pintype "passive"))
      (node (ref "J10") (pin "2") (pinfunction "2_2") (pintype "passive"))
      (node (ref "J3") (pin "2") (pinfunction "2_2") (pintype "passive"))
      (node (ref "J4") (pin "2") (pinfunction "2_2") (pintype "passive"))
      (node (ref "JP1") (pin "2") (pinfunction "2_2") (pintype "passive"))
      (node (ref "R1") (pin "2") (pinfunction "2_2") (pintype "passive"))
      (node (ref "R10") (pin "2") (pinfunction "2_2") (pintype "passive"))
      (node (ref "R12") (pin "2") (pinfunction "2_2") (pintype "passive"))
      (node (ref "R19") (pin "2") (pinfunction "2_2") (pintype "passive"))
      (node (ref "R2") (pin "1") (pinfunction "1_1") (pintype "passive"))
      (node (ref "R21") (pin "2") (pinfunction "2_2") (pintype "passive"))
      (node (ref "R22") (pin "2") (pinfunction "2_2") (pintype "passive"))
      (node (ref "R3") (pin "1") (pinfunction "1_1") (pintype "passive"))
      (node (ref "R4") (pin "2") (pinfunction "2_2") (pintype "passive"))
      (node (ref "R5") (pin "2") (pinfunction "2_2") (pintype "passive"))
      (node (ref "R6") (pin "2") (pinfunction "2_2") (pintype "passive"))
      (node (ref "R8") (pin "2") (pinfunction "2_2") (pintype "passive"))
      (node (ref "U1") (pin "5") (pinfunction "5_5") (pintype "passive"))
      (node (ref "U4") (pin "5") (pinfunction "5_5") (pintype "passive"))
      (node (ref "U5") (pin "5") (pinfunction "5_5") (pintype "passive"))
      (node (ref "U7") (pin "5") (pinfunction "5_5") (pintype "passive"))
    )
    (net (code "4") (name "+AREF") (class "Default")
      (node (ref "C17") (pin "2") (pinfunction "2_2") (pintype "passive"))
      (node (ref "C20") (pin "2") (pinfunction "2_2") (pintype "passive"))
      (node (ref "J5") (pin "8") (pinfunction "8_8") (pintype "passive"))
      (node (ref "U6") (pin "21") (pinfunction "AREF_21") (pintype "passive"))
    )
    (net (code "5") (name "/+5V_USB") (class "Default")
      (node (ref "C28") (pin "1") (pinfunction "1_1") (pintype "passive"))
      (node (ref "J9") (pin "1") (pinfunction "1_1") (pintype "passive"))
      (node (ref "L1") (pin "1") (pinfunction "1_1") (pintype "passive"))
    )
    (net (code "6") (name "/16U2PROG_328P_RESETn") (class "Default")
      (node (ref "JP3") (pin "2") (pinfunction "2_2") (pintype "passive"))
      (node (ref "R10") (pin "1") (pinfunction "1_1") (pintype "passive"))
      (node (ref "U3") (pin "13") (pinfunction "(~{HWB}_/_AIN6_/_T0_/_INT7)_PD7_13") (pintype "passive"))
    )
    (net (code "7") (name "/16U2_16MHz_XTAL1") (class "Default")
      (node (ref "C10") (pin "2") (pinfunction "2_2") (pintype "passive"))
      (node (ref "R15") (pin "2") (pinfunction "2_2") (pintype "passive"))
      (node (ref "U3") (pin "1") (pinfunction "XTAL1_1") (pintype "passive"))
      (node (ref "Y1") (pin "2") (pinfunction "2_2") (pintype "passive"))
    )
    (net (code "8") (name "/16U2_16MHz_XTAL2") (class "Default")
      (node (ref "C13") (pin "2") (pinfunction "2_2") (pintype "passive"))
      (node (ref "R15") (pin "1") (pinfunction "1_1") (pintype "passive"))
      (node (ref "U3") (pin "2") (pinfunction "(PC0)_XTAL2_2") (pintype "passive"))
      (node (ref "Y1") (pin "1") (pinfunction "1_1") (pintype "passive"))
    )
    (net (code "9") (name "/16U2_BUF_RESETn") (class "Default")
      (node (ref "C2") (pin "2") (pinfunction "2_2") (pintype "passive"))
      (node (ref "R7") (pin "2") (pinfunction "2_2") (pintype "passive"))
      (node (ref "U1") (pin "1") (pinfunction "1_1") (pintype "input"))
      (node (ref "U1") (pin "2") (pinfunction "2_2") (pintype "input"))
    )
    (net (code "10") (name "/16U2_HDR_RESETn") (class "Default")
      (node (ref "J4") (pin "5") (pinfunction "5_5") (pintype "passive"))
      (node (ref "JP2") (pin "3") (pinfunction "3_3") (pintype "passive"))
    )
    (net (code "11") (name "/16U2_MISO") (class "Default")
      (node (ref "J4") (pin "1") (pinfunction "1_1") (pintype "passive"))
      (node (ref "U3") (pin "17") (pinfunction "PB3_(PDO_/_MISO_/_PCINT3)_17") (pintype "passive"))
    )
    (net (code "12") (name "/16U2_MOSI") (class "Default")
      (node (ref "J4") (pin "4") (pinfunction "4_4") (pintype "passive"))
      (node (ref "U3") (pin "16") (pinfunction "(PDI_/_MOSI_/_PCINT2)_PB2_16") (pintype "passive"))
    )
    (net (code "13") (name "/16U2_PB4") (class "Default")
      (node (ref "J6") (pin "1") (pinfunction "1_1") (pintype "passive"))
      (node (ref "JP2") (pin "2") (pinfunction "2_2") (pintype "passive"))
      (node (ref "U3") (pin "18") (pinfunction "PB4_(T1_/_PCINT4)_18") (pintype "passive"))
    )
    (net (code "14") (name "/16U2_PB5") (class "Default")
      (node (ref "J6") (pin "3") (pinfunction "3_3") (pintype "passive"))
      (node (ref "U3") (pin "19") (pinfunction "PB5_(PCINT5)_19") (pintype "passive"))
    )
    (net (code "15") (name "/16U2_PB6") (class "Default")
      (node (ref "J6") (pin "2") (pinfunction "2_2") (pintype "passive"))
      (node (ref "U3") (pin "20") (pinfunction "PB6_(PCINT6)_20") (pintype "passive"))
    )
    (net (code "16") (name "/16U2_PB7") (class "Default")
      (node (ref "J6") (pin "4") (pinfunction "4_4") (pintype "passive"))
      (node (ref "U3") (pin "21") (pinfunction "PB7_(PCINT7_/_OC.0A_/_OC.1C)_21") (pintype "passive"))
    )
    (net (code "17") (name "/16U2_PD2") (class "Default")
      (node (ref "R14") (pin "1") (pinfunction "1_1") (pintype "passive"))
      (node (ref "U3") (pin "8") (pinfunction "(RXD1_/_AIN1_/_INT2)_PD2_8") (pintype "passive"))
    )
    (net (code "18") (name "/16U2_PD3") (class "Default")
      (node (ref "R11") (pin "1") (pinfunction "1_1") (pintype "passive"))
      (node (ref "U3") (pin "9") (pinfunction "(TXD1_/_INT3)_PD3_9") (pintype "passive"))
    )
    (net (code "19") (name "/16U2_RESETn") (class "Default")
      (node (ref "JP2") (pin "4") (pinfunction "4_4") (pintype "passive"))
      (node (ref "R8") (pin "1") (pinfunction "1_1") (pintype "passive"))
      (node (ref "U1") (pin "4") (pinfunction "4_4") (pintype "output"))
      (node (ref "U3") (pin "24") (pinfunction "~{Reset}_(PC1_/_dW)_24") (pintype "passive"))
    )
    (net (code "20") (name "/16U2_Rx_LED") (class "Default")
      (node (ref "D3") (pin "1") (pinfunction "Cathode_1") (pintype "passive"))
      (node (ref "U3") (pin "10") (pinfunction "(INT5/_AIN3)_PD4_10") (pintype "passive"))
    )
    (net (code "21") (name "/16U2_SCLK") (class "Default")
      (node (ref "J4") (pin "3") (pinfunction "3_3") (pintype "passive"))
      (node (ref "R18") (pin "1") (pinfunction "1_1") (pintype "passive"))
    )
    (net (code "22") (name "/16U2_SCLKR") (class "Default")
      (node (ref "R18") (pin "2") (pinfunction "2_2") (pintype "passive"))
      (node (ref "U3") (pin "15") (pinfunction "(SCLK_/_PCINT1)_PB1_15") (pintype "passive"))
    )
    (net (code "23") (name "/16U2_Tx_LED") (class "Default")
      (node (ref "D4") (pin "1") (pinfunction "Cathode_1") (pintype "passive"))
      (node (ref "U3") (pin "11") (pinfunction "(XCK_AIN4_/_PCINT12)_PD5_11") (pintype "passive"))
    )
    (net (code "24") (name "/16U2_UCAP") (class "Default")
      (node (ref "C11") (pin "2") (pinfunction "2_2") (pintype "passive"))
      (node (ref "R9") (pin "1") (pinfunction "1_1") (pintype "passive"))
      (node (ref "U3") (pin "27") (pinfunction "UCAP_27") (pintype "passive"))
    )
    (net (code "25") (name "/16U2_VCC") (class "Default")
      (node (ref "C5") (pin "2") (pinfunction "2_2") (pintype "passive"))
      (node (ref "C6") (pin "2") (pinfunction "2_2") (pintype "passive"))
      (node (ref "C7") (pin "2") (pinfunction "2_2") (pintype "passive"))
      (node (ref "FB1") (pin "2") (pinfunction "2_2") (pintype "passive"))
      (node (ref "R9") (pin "2") (pinfunction "2_2") (pintype "passive"))
      (node (ref "U3") (pin "32") (pinfunction "AVCC_32") (pintype "passive"))
      (node (ref "U3") (pin "4") (pinfunction "VCC_4") (pintype "passive"))
    )
    (net (code "26") (name "/328P_16MHz_XTAL1") (class "Default")
      (node (ref "C22") (pin "2") (pinfunction "2_2") (pintype "passive"))
      (node (ref "R25") (pin "2") (pinfunction "2_2") (pintype "passive"))
      (node (ref "U6") (pin "9") (pinfunction "(PCINT6/XTAL1/TOSC1)_PB6_9") (pintype "passive"))
      (node (ref "Y2") (pin "2") (pinfunction "2_2") (pintype "passive"))
    )
    (net (code "27") (name "/328P_16MHz_XTAL2") (class "Default")
      (node (ref "C25") (pin "2") (pinfunction "2_2") (pintype "passive"))
      (node (ref "R25") (pin "1") (pinfunction "1_1") (pintype "passive"))
      (node (ref "U6") (pin "10") (pinfunction "(PCINT7/XTAL2/TOSC2)_PB7_10") (pintype "passive"))
      (node (ref "Y2") (pin "1") (pinfunction "1_1") (pintype "passive"))
    )
    (net (code "28") (name "/328P_AUTORESETn") (class "Default")
      (node (ref "C19") (pin "1") (pinfunction "1_1") (pintype "passive"))
      (node (ref "R21") (pin "1") (pinfunction "1_1") (pintype "passive"))
      (node (ref "U7") (pin "1") (pinfunction "1_1") (pintype "input"))
    )
    (net (code "29") (name "/328P_AVCC") (class "Default")
      (node (ref "C32") (pin "2") (pinfunction "2_2") (pintype "passive"))
      (node (ref "C33") (pin "2") (pinfunction "2_2") (pintype "passive"))
      (node (ref "FB3") (pin "2") (pinfunction "2_2") (pintype "passive"))
      (node (ref "U6") (pin "20") (pinfunction "AVCC_20") (pintype "passive"))
    )
    (net (code "30") (name "/328P_BUF_RESETn") (class "Default")
      (node (ref "C21") (pin "2") (pinfunction "2_2") (pintype "passive"))
      (node (ref "R23") (pin "2") (pinfunction "2_2") (pintype "passive"))
      (node (ref "U7") (pin "2") (pinfunction "2_2") (pintype "input"))
    )
    (net (code "31") (name "/328P_MISO") (class "Default")
      (node (ref "J3") (pin "1") (pinfunction "1_1") (pintype "passive"))
      (node (ref "J5") (pin "5") (pinfunction "5_5") (pintype "passive"))
      (node (ref "U6") (pin "18") (pinfunction "PB4_(MISO/PCINT4)_18") (pintype "passive"))
    )
    (net (code "32") (name "/328P_MOSI") (class "Default")
      (node (ref "J3") (pin "4") (pinfunction "4_4") (pintype "passive"))
      (node (ref "J5") (pin "4") (pinfunction "4_4") (pintype "passive"))
      (node (ref "U6") (pin "17") (pinfunction "PB3_(MOSI/OC2A/PCINT3)_17") (pintype "passive"))
    )
    (net (code "33") (name "/328P_RESETn") (class "Default")
      (node (ref "J10") (pin "3") (pinfunction "3_3") (pintype "passive"))
      (node (ref "J3") (pin "5") (pinfunction "5_5") (pintype "passive"))
      (node (ref "JP2") (pin "1") (pinfunction "1_1") (pintype "passive"))
      (node (ref "R19") (pin "1") (pinfunction "1_1") (pintype "passive"))
      (node (ref "U6") (pin "1") (pinfunction "(PCINT14/~{RESET})_PC6_1") (pintype "passive"))
      (node (ref "U7") (pin "4") (pinfunction "4_4") (pintype "output"))
    )
    (net (code "34") (name "/328P_SCK") (class "Default")
      (node (ref "J3") (pin "3") (pinfunction "3_3") (pintype "passive"))
      (node (ref "J5") (pin "6") (pinfunction "6_6") (pintype "passive"))
      (node (ref "R20") (pin "2") (pinfunction "2_2") (pintype "passive"))
      (node (ref "U5") (pin "1") (pinfunction "1_1") (pintype "input"))
      (node (ref "U5") (pin "2") (pinfunction "2_2") (pintype "input"))
    )
    (net (code "35") (name "/328P_SCKR") (class "Default")
      (node (ref "R20") (pin "1") (pinfunction "1_1") (pintype "passive"))
      (node (ref "U6") (pin "19") (pinfunction "PB5_(SCK/PCINT5)_19") (pintype "passive"))
    )
    (net (code "36") (name "/328P_SS") (class "Default")
      (node (ref "J5") (pin "3") (pinfunction "3_3") (pintype "passive"))
      (node (ref "U6") (pin "16") (pinfunction "PB2_(SS/OC1B/PCINT2)_16") (pintype "passive"))
    )
    (net (code "37") (name "/328P_VCC") (class "Default")
      (node (ref "C26") (pin "2") (pinfunction "2_2") (pintype "passive"))
      (node (ref "C27") (pin "2") (pinfunction "2_2") (pintype "passive"))
      (node (ref "FB2") (pin "2") (pinfunction "2_2") (pintype "passive"))
      (node (ref "U6") (pin "7") (pinfunction "VCC_7") (pintype "passive"))
    )
    (net (code "38") (name "/AD0") (class "Default")
      (node (ref "J7") (pin "1") (pinfunction "1_1") (pintype "passive"))
      (node (ref "U6") (pin "23") (pinfunction "PC0_(ADC0/PCINT8)_23") (pintype "passive"))
    )
    (net (code "39") (name "/AD1") (class "Default")
      (node (ref "J7") (pin "2") (pinfunction "2_2") (pintype "passive"))
      (node (ref "U6") (pin "24") (pinfunction "PC1_(ADC1/PCINT9)_24") (pintype "passive"))
    )
    (net (code "40") (name "/AD2") (class "Default")
      (node (ref "J7") (pin "3") (pinfunction "3_3") (pintype "passive"))
      (node (ref "U6") (pin "25") (pinfunction "PC2_(ADC2/PCINT10)_25") (pintype "passive"))
    )
    (net (code "41") (name "/AD3") (class "Default")
      (node (ref "J7") (pin "4") (pinfunction "4_4") (pintype "passive"))
      (node (ref "U6") (pin "26") (pinfunction "PC3_(ADC3/PCINT11)_26") (pintype "passive"))
    )
    (net (code "42") (name "/AD4{slash}SDA") (class "Default")
      (node (ref "J5") (pin "9") (pinfunction "9_9") (pintype "passive"))
      (node (ref "J7") (pin "5") (pinfunction "5_5") (pintype "passive"))
      (node (ref "U6") (pin "27") (pinfunction "PC4_(ADC4/SDA/PCINT12)_27") (pintype "passive"))
    )
    (net (code "43") (name "/AD5{slash}SCL") (class "Default")
      (node (ref "J5") (pin "10") (pinfunction "10_10") (pintype "passive"))
      (node (ref "J7") (pin "6") (pinfunction "6_6") (pintype "passive"))
      (node (ref "U6") (pin "28") (pinfunction "PC5_(ADC5/SCL/PCINT13)_28") (pintype "passive"))
    )
    (net (code "44") (name "/BUTTON_RESETn") (class "Default")
      (node (ref "D6") (pin "2") (pinfunction "Anode_2") (pintype "passive"))
      (node (ref "R22") (pin "1") (pinfunction "1_1") (pintype "passive"))
      (node (ref "R23") (pin "1") (pinfunction "1_1") (pintype "passive"))
      (node (ref "SW2") (pin "3") (pinfunction "3_3") (pintype "passive"))
      (node (ref "SW2") (pin "4") (pinfunction "4_4") (pintype "passive"))
    )
    (net (code "45") (name "/CON_USB_N") (class "Default")
      (node (ref "J9") (pin "2") (pinfunction "2_2") (pintype "passive"))
      (node (ref "R28") (pin "1") (pinfunction "1_1") (pintype "passive"))
      (node (ref "Z2") (pin "2") (pinfunction "2_2") (pintype "passive"))
    )
    (net (code "46") (name "/CON_USB_P") (class "Default")
      (node (ref "J9") (pin "3") (pinfunction "3_3") (pintype "passive"))
      (node (ref "R27") (pin "1") (pinfunction "1_1") (pintype "passive"))
      (node (ref "Z1") (pin "2") (pinfunction "2_2") (pintype "passive"))
    )
    (net (code "47") (name "/IO0{slash}Rx") (class "Default")
      (node (ref "J8") (pin "1") (pinfunction "1_1") (pintype "passive"))
      (node (ref "R11") (pin "2") (pinfunction "2_2") (pintype "passive"))
      (node (ref "U6") (pin "2") (pinfunction "(PCINT16/RXD)_PD0_2") (pintype "passive"))
    )
    (net (code "48") (name "/IO1{slash}Tx") (class "Default")
      (node (ref "J8") (pin "2") (pinfunction "2_2") (pintype "passive"))
      (node (ref "R14") (pin "2") (pinfunction "2_2") (pintype "passive"))
      (node (ref "U6") (pin "3") (pinfunction "(PCINT17/TXD)_PD1_3") (pintype "passive"))
    )
    (net (code "49") (name "/IO2") (class "Default")
      (node (ref "J8") (pin "3") (pinfunction "3_3") (pintype "passive"))
      (node (ref "U6") (pin "4") (pinfunction "(PCINT18/INT0)_PD2_4") (pintype "passive"))
    )
    (net (code "50") (name "/IO3 ~") (class "Default")
      (node (ref "J8") (pin "4") (pinfunction "4_4") (pintype "passive"))
      (node (ref "U6") (pin "5") (pinfunction "(PCINT19/OC2B/INT1)_PD3_5") (pintype "passive"))
    )
    (net (code "51") (name "/IO4") (class "Default")
      (node (ref "J8") (pin "5") (pinfunction "5_5") (pintype "passive"))
      (node (ref "U6") (pin "6") (pinfunction "(PCINT20/XCK/T0)_PD4_6") (pintype "passive"))
    )
    (net (code "52") (name "/IO5 ~") (class "Default")
      (node (ref "J8") (pin "6") (pinfunction "6_6") (pintype "passive"))
      (node (ref "U6") (pin "11") (pinfunction "(PCINT21/OC0B/T1)_PD5_11") (pintype "passive"))
    )
    (net (code "53") (name "/IO6 ~") (class "Default")
      (node (ref "J8") (pin "7") (pinfunction "7_7") (pintype "passive"))
      (node (ref "U6") (pin "12") (pinfunction "(PCINT22/OC0A/AIN0)_PD6_12") (pintype "passive"))
    )
    (net (code "54") (name "/IO7") (class "Default")
      (node (ref "J8") (pin "8") (pinfunction "8_8") (pintype "passive"))
      (node (ref "U6") (pin "13") (pinfunction "(PCINT23/AIN1)_PD7_13") (pintype "passive"))
    )
    (net (code "55") (name "/IO8") (class "Default")
      (node (ref "J5") (pin "1") (pinfunction "1_1") (pintype "passive"))
      (node (ref "R16") (pin "2") (pinfunction "2_2") (pintype "passive"))
      (node (ref "U6") (pin "14") (pinfunction "(PCINT0/CLKO/ICP1)_PB0_14") (pintype "passive"))
    )
    (net (code "56") (name "/IO9") (class "Default")
      (node (ref "J5") (pin "2") (pinfunction "2_2") (pintype "passive"))
      (node (ref "U6") (pin "15") (pinfunction "PB1_(OC1A/PCINT1)_15") (pintype "passive"))
    )
    (net (code "57") (name "/USB_N") (class "Default")
      (node (ref "R28") (pin "2") (pinfunction "2_2") (pintype "passive"))
      (node (ref "U3") (pin "30") (pinfunction "D-_30") (pintype "passive"))
    )
    (net (code "58") (name "/USB_P") (class "Default")
      (node (ref "R27") (pin "2") (pinfunction "2_2") (pintype "passive"))
      (node (ref "U3") (pin "29") (pinfunction "D+_29") (pintype "passive"))
    )
    (net (code "59") (name "/USER_BUTTON") (class "Default")
      (node (ref "R12") (pin "1") (pinfunction "1_1") (pintype "passive"))
      (node (ref "R17") (pin "1") (pinfunction "1_1") (pintype "passive"))
      (node (ref "SW1") (pin "3") (pinfunction "3_3") (pintype "passive"))
      (node (ref "SW1") (pin "4") (pinfunction "4_4") (pintype "passive"))
    )
    (net (code "60") (name "/USER_BUTTON_BUF") (class "Default")
      (node (ref "C14") (pin "2") (pinfunction "2_2") (pintype "passive"))
      (node (ref "R17") (pin "2") (pinfunction "2_2") (pintype "passive"))
      (node (ref "U4") (pin "1") (pinfunction "1_1") (pintype "input"))
      (node (ref "U4") (pin "2") (pinfunction "2_2") (pintype "input"))
    )
    (net (code "61") (name "GND") (class "Default")
      (node (ref "C1") (pin "1") (pinfunction "1_1") (pintype "passive"))
      (node (ref "C10") (pin "1") (pinfunction "1_1") (pintype "passive"))
      (node (ref "C11") (pin "1") (pinfunction "1_1") (pintype "passive"))
      (node (ref "C12") (pin "1") (pinfunction "1_1") (pintype "passive"))
      (node (ref "C13") (pin "1") (pinfunction "1_1") (pintype "passive"))
      (node (ref "C14") (pin "1") (pinfunction "1_1") (pintype "passive"))
      (node (ref "C15") (pin "1") (pinfunction "1_1") (pintype "passive"))
      (node (ref "C16") (pin "1") (pinfunction "1_1") (pintype "passive"))
      (node (ref "C17") (pin "1") (pinfunction "1_1") (pintype "passive"))
      (node (ref "C18") (pin "1") (pinfunction "1_1") (pintype "passive"))
      (node (ref "C2") (pin "1") (pinfunction "1_1") (pintype "passive"))
      (node (ref "C20") (pin "1") (pinfunction "1_1") (pintype "passive"))
      (node (ref "C21") (pin "1") (pinfunction "1_1") (pintype "passive"))
      (node (ref "C22") (pin "1") (pinfunction "1_1") (pintype "passive"))
      (node (ref "C23") (pin "1") (pinfunction "1_1") (pintype "passive"))
      (node (ref "C24") (pin "1") (pinfunction "1_1") (pintype "passive"))
      (node (ref "C25") (pin "1") (pinfunction "1_1") (pintype "passive"))
      (node (ref "C26") (pin "1") (pinfunction "1_1") (pintype "passive"))
      (node (ref "C27") (pin "1") (pinfunction "1_1") (pintype "passive"))
      (node (ref "C28") (pin "2") (pinfunction "2_2") (pintype "passive"))
      (node (ref "C29") (pin "2") (pinfunction "2_2") (pintype "passive"))
      (node (ref "C3") (pin "1") (pinfunction "1_1") (pintype "passive"))
      (node (ref "C30") (pin "1") (pinfunction "1_1") (pintype "passive"))
      (node (ref "C31") (pin "1") (pinfunction "1_1") (pintype "passive"))
      (node (ref "C32") (pin "1") (pinfunction "1_1") (pintype "passive"))
      (node (ref "C33") (pin "1") (pinfunction "1_1") (pintype "passive"))
      (node (ref "C4") (pin "1") (pinfunction "1_1") (pintype "passive"))
      (node (ref "C5") (pin "1") (pinfunction "1_1") (pintype "passive"))
      (node (ref "C6") (pin "1") (pinfunction "1_1") (pintype "passive"))
      (node (ref "C7") (pin "1") (pinfunction "1_1") (pintype "passive"))
      (node (ref "C8") (pin "1") (pinfunction "1_1") (pintype "passive"))
      (node (ref "C9") (pin "1") (pinfunction "1_1") (pintype "passive"))
      (node (ref "D1") (pin "1") (pinfunction "Cathode_1") (pintype "passive"))
      (node (ref "J10") (pin "6") (pinfunction "6_6") (pintype "passive"))
      (node (ref "J10") (pin "7") (pinfunction "7_7") (pintype "passive"))
      (node (ref "J2") (pin "1") (pinfunction "1_1") (pintype "passive"))
      (node (ref "J3") (pin "6") (pinfunction "6_6") (pintype "passive"))
      (node (ref "J4") (pin "6") (pinfunction "6_6") (pintype "passive"))
      (node (ref "J5") (pin "7") (pinfunction "7_7") (pintype "passive"))
      (node (ref "J9") (pin "10") (pintype "passive"))
      (node (ref "J9") (pin "11") (pintype "passive"))
      (node (ref "J9") (pin "5") (pinfunction "5_5") (pintype "passive"))
      (node (ref "J9") (pin "6") (pintype "passive"))
      (node (ref "J9") (pin "7") (pintype "passive"))
      (node (ref "J9") (pin "8") (pintype "passive"))
      (node (ref "J9") (pin "9") (pintype "passive"))
      (node (ref "MH1") (pin "1") (pinfunction "1_1") (pintype "passive"))
      (node (ref "MH2") (pin "1") (pinfunction "1_1") (pintype "passive"))
      (node (ref "MH3") (pin "1") (pinfunction "1_1") (pintype "passive"))
      (node (ref "R24") (pin "1") (pinfunction "1_1") (pintype "passive"))
      (node (ref "R26") (pin "2") (pinfunction "2_2") (pintype "passive"))
      (node (ref "SW1") (pin "1") (pinfunction "1_1") (pintype "passive"))
      (node (ref "SW1") (pin "2") (pinfunction "2_2") (pintype "passive"))
      (node (ref "SW2") (pin "1") (pinfunction "1_1") (pintype "passive"))
      (node (ref "SW2") (pin "2") (pinfunction "2_2") (pintype "passive"))
      (node (ref "U1") (pin "3") (pinfunction "3_3") (pintype "passive"))
      (node (ref "U2") (pin "3") (pinfunction "GND_3") (pintype "passive"))
      (node (ref "U2") (pin "6") (pinfunction "EPAD_6") (pintype "passive"))
      (node (ref "U3") (pin "28") (pinfunction "UGND_28") (pintype "passive"))
      (node (ref "U3") (pin "3") (pinfunction "GND_3") (pintype "passive"))
      (node (ref "U4") (pin "3") (pinfunction "3_3") (pintype "passive"))
      (node (ref "U5") (pin "3") (pinfunction "3_3") (pintype "passive"))
      (node (ref "U6") (pin "22") (pinfunction "GND_22") (pintype "passive"))
      (node (ref "U6") (pin "8") (pinfunction "GND_8") (pintype "passive"))
      (node (ref "U7") (pin "3") (pinfunction "3_3") (pintype "passive"))
      (node (ref "Z1") (pin "1") (pinfunction "1_1") (pintype "passive"))
      (node (ref "Z2") (pin "1") (pinfunction "1_1") (pintype "passive"))
    )
    (net (code "62") (name "Net-(C19-Pad2)") (class "Default")
      (node (ref "C19") (pin "2") (pinfunction "2_2") (pintype "passive"))
      (node (ref "JP3") (pin "1") (pinfunction "1_1") (pintype "passive"))
    )
    (net (code "63") (name "Net-(D1-Anode)") (class "Default")
      (node (ref "D1") (pin "2") (pinfunction "Anode_2") (pintype "passive"))
      (node (ref "R6") (pin "1") (pinfunction "1_1") (pintype "passive"))
    )
    (net (code "64") (name "Net-(D2-Anode)") (class "Default")
      (node (ref "D2") (pin "2") (pinfunction "Anode_2") (pintype "passive"))
      (node (ref "R5") (pin "1") (pinfunction "1_1") (pintype "passive"))
      (node (ref "R7") (pin "1") (pinfunction "1_1") (pintype "passive"))
    )
    (net (code "65") (name "Net-(D3-Anode)") (class "Default")
      (node (ref "D3") (pin "2") (pinfunction "Anode_2") (pintype "passive"))
      (node (ref "R3") (pin "2") (pinfunction "2_2") (pintype "passive"))
    )
    (net (code "66") (name "Net-(D4-Anode)") (class "Default")
      (node (ref "D4") (pin "2") (pinfunction "Anode_2") (pintype "passive"))
      (node (ref "R4") (pin "1") (pinfunction "1_1") (pintype "passive"))
    )
    (net (code "67") (name "Net-(D5-Anode)") (class "Default")
      (node (ref "D5") (pin "2") (pinfunction "Anode_2") (pintype "passive"))
      (node (ref "R13") (pin "2") (pinfunction "2_2") (pintype "passive"))
    )
    (net (code "68") (name "Net-(J9-Pad4)") (class "Default")
      (node (ref "J9") (pin "4") (pinfunction "4_4") (pintype "passive"))
      (node (ref "R26") (pin "1") (pinfunction "1_1") (pintype "passive"))
    )
    (net (code "69") (name "Net-(JP3-Pad3)") (class "Default")
      (node (ref "JP3") (pin "3") (pinfunction "3_3") (pintype "passive"))
      (node (ref "R24") (pin "2") (pinfunction "2_2") (pintype "passive"))
    )
    (net (code "70") (name "Net-(R13-Pad1)") (class "Default")
      (node (ref "R13") (pin "1") (pinfunction "1_1") (pintype "passive"))
      (node (ref "U5") (pin "4") (pinfunction "4_4") (pintype "output"))
    )
    (net (code "71") (name "Net-(R16-Pad1)") (class "Default")
      (node (ref "R16") (pin "1") (pinfunction "1_1") (pintype "passive"))
      (node (ref "U4") (pin "4") (pinfunction "4_4") (pintype "output"))
    )
    (net (code "72") (name "unconnected-(J10-Pad1)") (class "Default")
      (node (ref "J10") (pin "1") (pinfunction "1_1") (pintype "passive+no_connect"))
    )
    (net (code "73") (name "unconnected-(J10-Pad8)") (class "Default")
      (node (ref "J10") (pin "8") (pinfunction "8_8") (pintype "passive+no_connect"))
    )
    (net (code "74") (name "unconnected-(MH4-Pad1)") (class "Default")
      (node (ref "MH4") (pin "1") (pinfunction "1_1") (pintype "passive+no_connect"))
    )
    (net (code "75") (name "unconnected-(U3-(AIN0_{slash}_INT1)_PD1-Pad7)") (class "Default")
      (node (ref "U3") (pin "7") (pinfunction "(AIN0_/_INT1)_PD1_7") (pintype "passive+no_connect"))
    )
    (net (code "76") (name "unconnected-(U3-(OC.0B_{slash}_INT0)_PD0-Pad6)") (class "Default")
      (node (ref "U3") (pin "6") (pinfunction "(OC.0B_/_INT0)_PD0_6") (pintype "passive+no_connect"))
    )
    (net (code "77") (name "unconnected-(U3-(PCINT11_{slash}AIN2_)_PC2-Pad5)") (class "Default")
      (node (ref "U3") (pin "5") (pinfunction "(PCINT11_/AIN2_)_PC2_5") (pintype "passive+no_connect"))
    )
    (net (code "78") (name "unconnected-(U3-(SS_{slash}_PCINT0)_PB0-Pad14)") (class "Default")
      (node (ref "U3") (pin "14") (pinfunction "(SS_/_PCINT0)_PB0_14") (pintype "passive"))
    )
    (net (code "79") (name "unconnected-(U3-(~{RTS}_{slash}_AIN5_{slash}_INT6)_PD6-Pad12)") (class "Default")
      (node (ref "U3") (pin "12") (pinfunction "(~{RTS}_/_AIN5_/_INT6)_PD6_12") (pintype "passive+no_connect"))
    )
    (net (code "80") (name "unconnected-(U3-PC4_(PCINT10)-Pad26)") (class "Default")
      (node (ref "U3") (pin "26") (pinfunction "PC4_(PCINT10)_26") (pintype "passive+no_connect"))
    )
    (net (code "81") (name "unconnected-(U3-PC5_(_PCINT9{slash}_OC.1B)-Pad25)") (class "Default")
      (node (ref "U3") (pin "25") (pinfunction "PC5_(_PCINT9/_OC.1B)_25") (pintype "passive+no_connect"))
    )
    (net (code "82") (name "unconnected-(U3-PC6_(OC.1A_{slash}_PCINT8)-Pad23)") (class "Default")
      (node (ref "U3") (pin "23") (pinfunction "PC6_(OC.1A_/_PCINT8)_23") (pintype "passive+no_connect"))
    )
    (net (code "83") (name "unconnected-(U3-PC7_(INT4_{slash}_ICP1_{slash}_CLKO)-Pad22)") (class "Default")
      (node (ref "U3") (pin "22") (pinfunction "PC7_(INT4_/_ICP1_/_CLKO)_22") (pintype "passive+no_connect"))
    )
  )
)
